# Half_Bridge.net
KiCad netlist of a schematic drawn in EAGLE
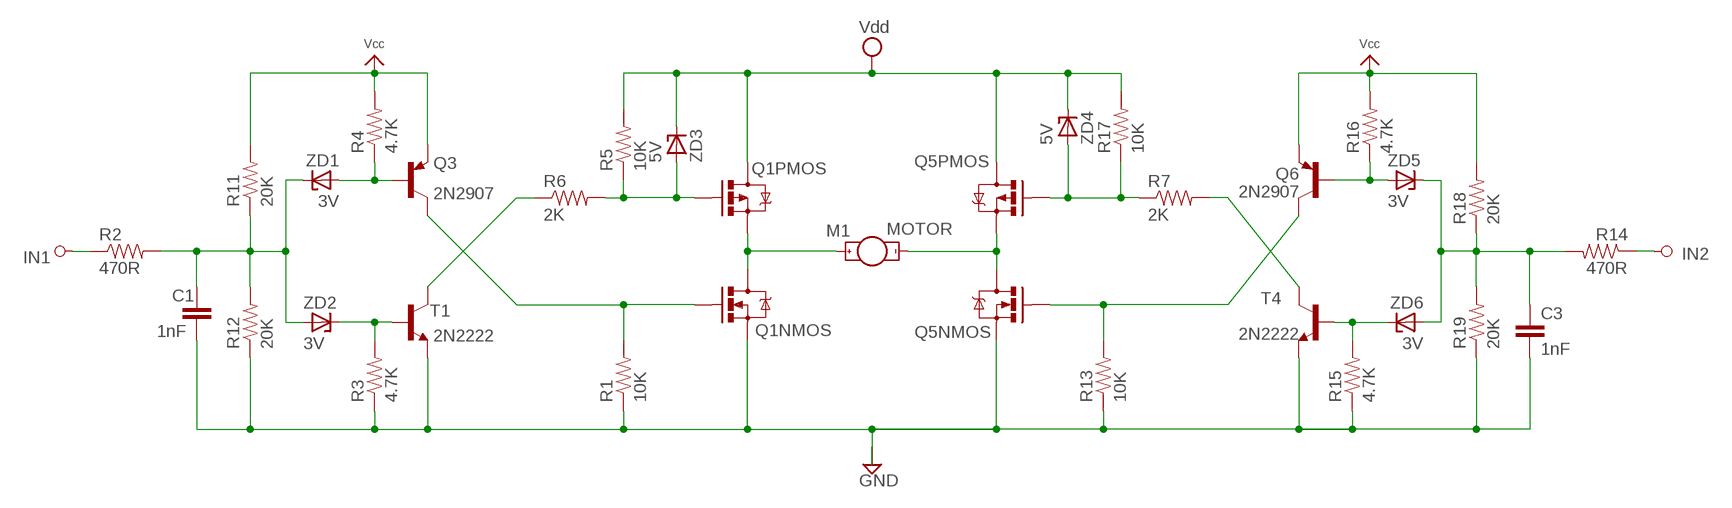
[diagram p0: schematic, sheet 1]

(export (version "E")
  (design (tool "Eeschema 10.0.6"))
  (components
    (comp (ref "C1")
      (value "1nF")
      (footprint "eagle-import:0805")
      (libsource (lib "eagle-import") (part "CAP0805"))
    )
    (comp (ref "C3")
      (value "1nF")
      (footprint "eagle-import:0805")
      (libsource (lib "eagle-import") (part "CAP0805"))
    )
    (comp (ref "IN1")
      (value "IN1")
      (footprint "eagle-import:PAD_ROUND_4.1MM")
      (libsource (lib "eagle-import") (part "PAD_TERMINAL-4.1MMROUND"))
    )
    (comp (ref "IN2")
      (value "PAD_TERMINAL-4.1MMROUND")
      (footprint "eagle-import:PAD_ROUND_4.1MM")
      (libsource (lib "eagle-import") (part "PAD_TERMINAL-4.1MMROUND"))
    )
    (comp (ref "M1")
      (value "MOTOR")
      (footprint "eagle-import:VIBE-MOTOR-10MM")
      (libsource (lib "eagle-import") (part "MOTOR10MM"))
    )
    (comp (ref "Q1")
      (value "IRF7509")
      (footprint "eagle-import:MSOP8")
      (libsource (lib "eagle-import") (part "IRF7509"))
    )
    (comp (ref "Q3")
      (value "2N2907")
      (footprint "eagle-import:TO92-EBC-OVAL")
      (libsource (lib "eagle-import") (part "2N2907"))
    )
    (comp (ref "Q5")
      (value "IRF7509")
      (footprint "eagle-import:MSOP8")
      (libsource (lib "eagle-import") (part "IRF7509"))
    )
    (comp (ref "Q6")
      (value "2N2907")
      (footprint "eagle-import:TO92-EBC-OVAL")
      (libsource (lib "eagle-import") (part "2N2907"))
    )
    (comp (ref "R1")
      (value "10K")
      (footprint "eagle-import:0805")
      (libsource (lib "eagle-import") (part "RESISTOR0805-RES"))
    )
    (comp (ref "R2")
      (value "470R")
      (footprint "eagle-import:0805")
      (libsource (lib "eagle-import") (part "RESISTOR0805-RES"))
    )
    (comp (ref "R3")
      (value "4.7K")
      (footprint "eagle-import:0805")
      (libsource (lib "eagle-import") (part "RESISTOR0805-RES"))
    )
    (comp (ref "R4")
      (value "4.7K")
      (footprint "eagle-import:0805")
      (libsource (lib "eagle-import") (part "RESISTOR0805-RES"))
    )
    (comp (ref "R5")
      (value "10K")
      (footprint "eagle-import:0805")
      (libsource (lib "eagle-import") (part "RESISTOR0805-RES"))
    )
    (comp (ref "R6")
      (value "2K")
      (footprint "eagle-import:0805")
      (libsource (lib "eagle-import") (part "RESISTOR0805-RES"))
    )
    (comp (ref "R7")
      (value "2K")
      (footprint "eagle-import:0805")
      (libsource (lib "eagle-import") (part "RESISTOR0805-RES"))
    )
    (comp (ref "R11")
      (value "20K")
      (footprint "eagle-import:0805")
      (libsource (lib "eagle-import") (part "RESISTOR0805-RES"))
    )
    (comp (ref "R12")
      (value "20K")
      (footprint "eagle-import:0805")
      (libsource (lib "eagle-import") (part "RESISTOR0805-RES"))
    )
    (comp (ref "R13")
      (value "10K")
      (footprint "eagle-import:0805")
      (libsource (lib "eagle-import") (part "RESISTOR0805-RES"))
    )
    (comp (ref "R14")
      (value "470R")
      (footprint "eagle-import:0805")
      (libsource (lib "eagle-import") (part "RESISTOR0805-RES"))
    )
    (comp (ref "R15")
      (value "4.7K")
      (footprint "eagle-import:0805")
      (libsource (lib "eagle-import") (part "RESISTOR0805-RES"))
    )
    (comp (ref "R16")
      (value "4.7K")
      (footprint "eagle-import:0805")
      (libsource (lib "eagle-import") (part "RESISTOR0805-RES"))
    )
    (comp (ref "R17")
      (value "10K")
      (footprint "eagle-import:0805")
      (libsource (lib "eagle-import") (part "RESISTOR0805-RES"))
    )
    (comp (ref "R18")
      (value "20K")
      (footprint "eagle-import:0805")
      (libsource (lib "eagle-import") (part "RESISTOR0805-RES"))
    )
    (comp (ref "R19")
      (value "20K")
      (footprint "eagle-import:0805")
      (libsource (lib "eagle-import") (part "RESISTOR0805-RES"))
    )
    (comp (ref "T1")
      (value "2N2222")
      (footprint "eagle-import:TO92-EBC-OVAL")
      (libsource (lib "eagle-import") (part "2N2222"))
    )
    (comp (ref "T4")
      (value "2N2222")
      (footprint "eagle-import:TO92-EBC-OVAL")
      (libsource (lib "eagle-import") (part "2N2222"))
    )
    (comp (ref "ZD1")
      (value "3V")
      (footprint "eagle-import:SOD-123")
      (libsource (lib "eagle-import") (part "ZENERSOD-123"))
    )
    (comp (ref "ZD2")
      (value "3V")
      (footprint "eagle-import:SOD-123")
      (libsource (lib "eagle-import") (part "ZENERSOD-123"))
    )
    (comp (ref "ZD3")
      (value "5V")
      (footprint "eagle-import:SOD-123")
      (libsource (lib "eagle-import") (part "ZENERSOD-123"))
    )
    (comp (ref "ZD4")
      (value "5V")
      (footprint "eagle-import:SOD-123")
      (libsource (lib "eagle-import") (part "ZENERSOD-123"))
    )
    (comp (ref "ZD5")
      (value "3V")
      (footprint "eagle-import:SOD-123")
      (libsource (lib "eagle-import") (part "ZENERSOD-123"))
    )
    (comp (ref "ZD6")
      (value "3V")
      (footprint "eagle-import:SOD-123")
      (libsource (lib "eagle-import") (part "ZENERSOD-123"))
    )
  )
  (nets
    (net (code "1") (name "GND") (class "Default")
      (node (ref "C1") (pin "2") (pinfunction "2_2") (pintype "passive"))
      (node (ref "C3") (pin "2") (pinfunction "2_2") (pintype "passive"))
      (node (ref "Q1") (pin "1") (pinfunction "S_1") (pintype "passive"))
      (node (ref "Q5") (pin "1") (pinfunction "S_1") (pintype "passive"))
      (node (ref "R1") (pin "1") (pinfunction "1_1") (pintype "passive"))
      (node (ref "R12") (pin "1") (pinfunction "1_1") (pintype "passive"))
      (node (ref "R13") (pin "1") (pinfunction "1_1") (pintype "passive"))
      (node (ref "R15") (pin "1") (pinfunction "1_1") (pintype "passive"))
      (node (ref "R19") (pin "1") (pinfunction "1_1") (pintype "passive"))
      (node (ref "R3") (pin "1") (pinfunction "1_1") (pintype "passive"))
      (node (ref "T1") (pin "E") (pinfunction "E_E") (pintype "passive"))
      (node (ref "T4") (pin "E") (pinfunction "E_E") (pintype "passive"))
    )
    (net (code "2") (name "Net-(C1-Pad1)") (class "Default")
      (node (ref "C1") (pin "1") (pinfunction "1_1") (pintype "passive"))
      (node (ref "R11") (pin "1") (pinfunction "1_1") (pintype "passive"))
      (node (ref "R12") (pin "2") (pinfunction "2_2") (pintype "passive"))
      (node (ref "R2") (pin "2") (pinfunction "2_2") (pintype "passive"))
      (node (ref "ZD1") (pin "C") (pinfunction "C_C") (pintype "passive"))
      (node (ref "ZD2") (pin "A") (pinfunction "A_A") (pintype "passive"))
    )
    (net (code "3") (name "Net-(C3-Pad1)") (class "Default")
      (node (ref "C3") (pin "1") (pinfunction "1_1") (pintype "passive"))
      (node (ref "R14") (pin "2") (pinfunction "2_2") (pintype "passive"))
      (node (ref "R18") (pin "1") (pinfunction "1_1") (pintype "passive"))
      (node (ref "R19") (pin "2") (pinfunction "2_2") (pintype "passive"))
      (node (ref "ZD5") (pin "C") (pinfunction "C_C") (pintype "passive"))
      (node (ref "ZD6") (pin "A") (pinfunction "A_A") (pintype "passive"))
    )
    (net (code "4") (name "Net-(IN1-PadP)") (class "Default")
      (node (ref "IN1") (pin "P") (pinfunction "P_P") (pintype "passive"))
      (node (ref "R2") (pin "1") (pinfunction "1_1") (pintype "passive"))
    )
    (net (code "5") (name "Net-(IN2-PadP)") (class "Default")
      (node (ref "IN2") (pin "P") (pinfunction "P_P") (pintype "passive"))
      (node (ref "R14") (pin "1") (pinfunction "1_1") (pintype "passive"))
    )
    (net (code "6") (name "Net-(Q1A-G)") (class "Default")
      (node (ref "Q1") (pin "2") (pinfunction "G_2") (pintype "passive"))
      (node (ref "Q3") (pin "C") (pinfunction "C_C") (pintype "passive"))
      (node (ref "R1") (pin "2") (pinfunction "2_2") (pintype "passive"))
    )
    (net (code "7") (name "Net-(Q1B-G)") (class "Default")
      (node (ref "Q1") (pin "4") (pinfunction "G_4") (pintype "passive"))
      (node (ref "R5") (pin "1") (pinfunction "1_1") (pintype "passive"))
      (node (ref "R6") (pin "2") (pinfunction "2_2") (pintype "passive"))
      (node (ref "ZD3") (pin "A") (pinfunction "A_A") (pintype "passive"))
    )
    (net (code "8") (name "Net-(Q1B-S)") (class "Default")
      (node (ref "M1") (pin "+") (pinfunction "+_+") (pintype "bidirectional"))
      (node (ref "Q1") (pin "3") (pinfunction "S_3") (pintype "passive"))
      (node (ref "Q1") (pin "7") (pinfunction "D_7") (pintype "passive"))
      (node (ref "Q1") (pin "8") (pinfunction "D_8") (pintype "passive"))
    )
    (net (code "9") (name "Net-(Q3-PadB)") (class "Default")
      (node (ref "Q3") (pin "B") (pinfunction "B_B") (pintype "passive"))
      (node (ref "R4") (pin "1") (pinfunction "1_1") (pintype "passive"))
      (node (ref "ZD1") (pin "A") (pinfunction "A_A") (pintype "passive"))
    )
    (net (code "10") (name "Net-(Q5A-G)") (class "Default")
      (node (ref "Q5") (pin "2") (pinfunction "G_2") (pintype "passive"))
      (node (ref "Q6") (pin "C") (pinfunction "C_C") (pintype "passive"))
      (node (ref "R13") (pin "2") (pinfunction "2_2") (pintype "passive"))
    )
    (net (code "11") (name "Net-(Q5B-G)") (class "Default")
      (node (ref "Q5") (pin "4") (pinfunction "G_4") (pintype "passive"))
      (node (ref "R17") (pin "1") (pinfunction "1_1") (pintype "passive"))
      (node (ref "R7") (pin "1") (pinfunction "1_1") (pintype "passive"))
      (node (ref "ZD4") (pin "A") (pinfunction "A_A") (pintype "passive"))
    )
    (net (code "12") (name "Net-(Q5B-S)") (class "Default")
      (node (ref "M1") (pin "-") (pinfunction "-_-") (pintype "bidirectional"))
      (node (ref "Q5") (pin "3") (pinfunction "S_3") (pintype "passive"))
      (node (ref "Q5") (pin "7") (pinfunction "D_7") (pintype "passive"))
      (node (ref "Q5") (pin "8") (pinfunction "D_8") (pintype "passive"))
    )
    (net (code "13") (name "Net-(Q6-PadB)") (class "Default")
      (node (ref "Q6") (pin "B") (pinfunction "B_B") (pintype "passive"))
      (node (ref "R16") (pin "1") (pinfunction "1_1") (pintype "passive"))
      (node (ref "ZD5") (pin "A") (pinfunction "A_A") (pintype "passive"))
    )
    (net (code "14") (name "Net-(R3-Pad2)") (class "Default")
      (node (ref "R3") (pin "2") (pinfunction "2_2") (pintype "passive"))
      (node (ref "T1") (pin "B") (pinfunction "B_B") (pintype "passive"))
      (node (ref "ZD2") (pin "C") (pinfunction "C_C") (pintype "passive"))
    )
    (net (code "15") (name "Net-(R6-Pad1)") (class "Default")
      (node (ref "R6") (pin "1") (pinfunction "1_1") (pintype "passive"))
      (node (ref "T1") (pin "C") (pinfunction "C_C") (pintype "passive"))
    )
    (net (code "16") (name "Net-(R7-Pad2)") (class "Default")
      (node (ref "R7") (pin "2") (pinfunction "2_2") (pintype "passive"))
      (node (ref "T4") (pin "C") (pinfunction "C_C") (pintype "passive"))
    )
    (net (code "17") (name "Net-(R15-Pad2)") (class "Default")
      (node (ref "R15") (pin "2") (pinfunction "2_2") (pintype "passive"))
      (node (ref "T4") (pin "B") (pinfunction "B_B") (pintype "passive"))
      (node (ref "ZD6") (pin "C") (pinfunction "C_C") (pintype "passive"))
    )
    (net (code "18") (name "Vcc") (class "Default")
      (node (ref "Q1") (pin "5") (pinfunction "D_5") (pintype "passive"))
      (node (ref "Q1") (pin "6") (pinfunction "D_6") (pintype "passive"))
      (node (ref "Q3") (pin "E") (pinfunction "E_E") (pintype "passive"))
      (node (ref "Q5") (pin "5") (pinfunction "D_5") (pintype "passive"))
      (node (ref "Q5") (pin "6") (pinfunction "D_6") (pintype "passive"))
      (node (ref "Q6") (pin "E") (pinfunction "E_E") (pintype "passive"))
      (node (ref "R11") (pin "2") (pinfunction "2_2") (pintype "passive"))
      (node (ref "R16") (pin "2") (pinfunction "2_2") (pintype "passive"))
      (node (ref "R17") (pin "2") (pinfunction "2_2") (pintype "passive"))
      (node (ref "R18") (pin "2") (pinfunction "2_2") (pintype "passive"))
      (node (ref "R4") (pin "2") (pinfunction "2_2") (pintype "passive"))
      (node (ref "R5") (pin "2") (pinfunction "2_2") (pintype "passive"))
      (node (ref "ZD3") (pin "C") (pinfunction "C_C") (pintype "passive"))
      (node (ref "ZD4") (pin "C") (pinfunction "C_C") (pintype "passive"))
    )
  )
)
